# sensors.net
KiCad netlist of a schematic drawn in Altium Designer
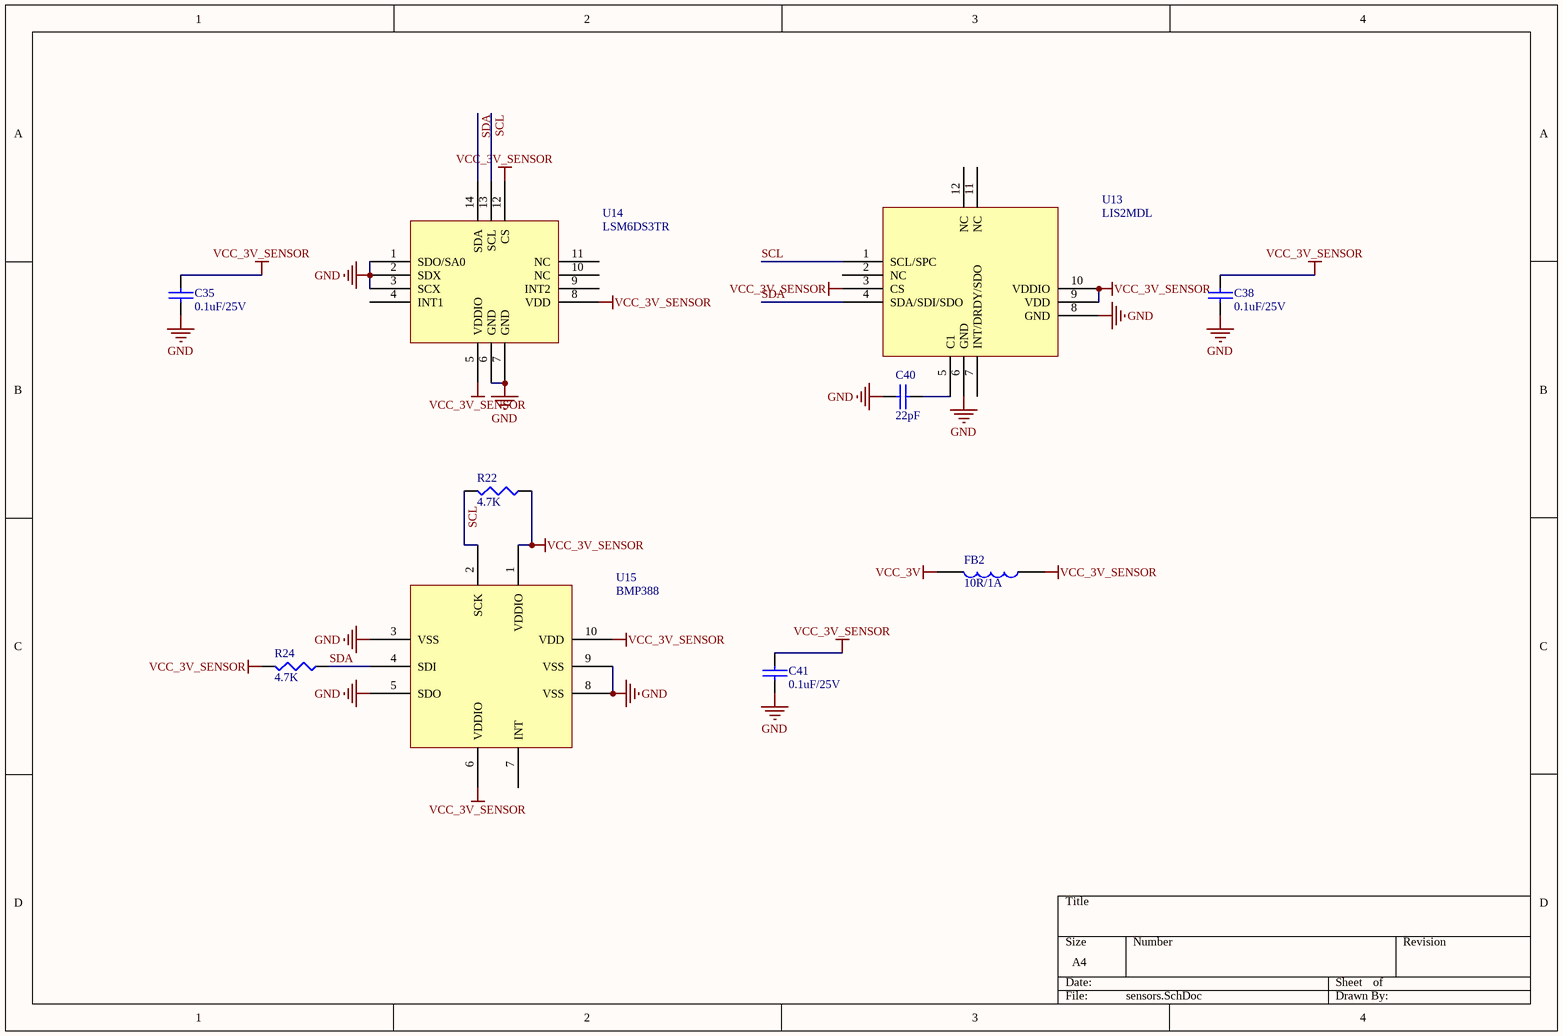
[diagram p0: sensors.SchDoc]

(export (version "E")
  (design (tool "Eeschema 10.0.6"))
  (components
    (comp (ref "C35")
      (value "0.1uF/25V")
      (footprint "0402C")
      (description "Capacitor")
      (libsource (lib "ZWLIntegrated_Library") (part "CAP"))
    )
    (comp (ref "C38")
      (value "0.1uF/25V")
      (footprint "0402C")
      (description "Capacitor")
      (libsource (lib "ZWLIntegrated_Library") (part "CAP"))
    )
    (comp (ref "C40")
      (value "22pF")
      (footprint "0402c")
      (description "Capacitor")
      (libsource (lib "SM") (part "CAP"))
    )
    (comp (ref "C41")
      (value "0.1uF/25V")
      (footprint "0402C")
      (description "Capacitor")
      (libsource (lib "ZWLIntegrated_Library") (part "CAP"))
    )
    (comp (ref "FB2") (value "10R/1A") (footprint "0603R") (libsource (lib "*") (part "INDUCTOR1")))
    (comp (ref "R22")
      (value "4.7K")
      (footprint "0402R")
      (libsource (lib "ZWLIntegrated_Library") (part "RES1"))
    )
    (comp (ref "R24")
      (value "4.7K")
      (footprint "0402R")
      (libsource (lib "ZWLIntegrated_Library") (part "RES1"))
    )
    (comp (ref "U13") (value "LIS2MDL") (footprint "LIS2MDL") (libsource (lib "stm32") (part "LIS2MDL")))
    (comp (ref "U14")
      (value "LSM6DS3TR")
      (footprint "LSM6DS3TR-C")
      (libsource (lib "stm32") (part "LSM6DS3TR"))
    )
    (comp (ref "U15") (value "BMP388") (footprint "BMP388") (libsource (lib "stm32") (part "BMP388")))
  )
  (nets
    (net (code "1") (name "/SCL") (class "Default")
      (node (ref "R22") (pin "2") (pinfunction "2_2") (pintype "passive"))
      (node (ref "U13") (pin "1") (pinfunction "SCL/SPC_1") (pintype "passive"))
      (node (ref "U14") (pin "13") (pinfunction "SCL_13") (pintype "passive"))
      (node (ref "U15") (pin "2") (pinfunction "SCK_2") (pintype "passive"))
    )
    (net (code "2") (name "/SDA") (class "Default")
      (node (ref "R24") (pin "1") (pinfunction "1_1") (pintype "passive"))
      (node (ref "U13") (pin "4") (pinfunction "SDA/SDI/SDO_4") (pintype "passive"))
      (node (ref "U14") (pin "14") (pinfunction "SDA_14") (pintype "passive"))
      (node (ref "U15") (pin "4") (pinfunction "SDI_4") (pintype "passive"))
    )
    (net (code "3") (name "GND") (class "Default")
      (node (ref "C35") (pin "1") (pinfunction "1_1") (pintype "passive"))
      (node (ref "C38") (pin "1") (pinfunction "1_1") (pintype "passive"))
      (node (ref "C40") (pin "2") (pinfunction "2_2") (pintype "passive"))
      (node (ref "C41") (pin "1") (pinfunction "1_1") (pintype "passive"))
      (node (ref "U13") (pin "6") (pinfunction "GND_6") (pintype "passive"))
      (node (ref "U13") (pin "8") (pinfunction "GND_8") (pintype "passive"))
      (node (ref "U14") (pin "1") (pinfunction "SDO/SA0_1") (pintype "passive"))
      (node (ref "U14") (pin "2") (pinfunction "SDX_2") (pintype "passive"))
      (node (ref "U14") (pin "3") (pinfunction "SCX_3") (pintype "passive"))
      (node (ref "U14") (pin "6") (pinfunction "GND_6") (pintype "passive"))
      (node (ref "U14") (pin "7") (pinfunction "GND_7") (pintype "passive"))
      (node (ref "U15") (pin "3") (pinfunction "VSS_3") (pintype "passive"))
      (node (ref "U15") (pin "5") (pinfunction "SDO_5") (pintype "passive"))
      (node (ref "U15") (pin "8") (pinfunction "VSS_8") (pintype "passive"))
      (node (ref "U15") (pin "9") (pinfunction "VSS_9") (pintype "passive"))
    )
    (net (code "4") (name "Net-(U13-C1)") (class "Default")
      (node (ref "C40") (pin "1") (pinfunction "1_1") (pintype "passive"))
      (node (ref "U13") (pin "5") (pinfunction "C1_5") (pintype "passive"))
    )
    (net (code "5") (name "VCC_3V") (class "Default")
      (node (ref "FB2") (pin "1") (pinfunction "1_1") (pintype "passive"))
    )
    (net (code "6") (name "VCC_3V_SENSOR") (class "Default")
      (node (ref "C35") (pin "2") (pinfunction "2_2") (pintype "passive"))
      (node (ref "C38") (pin "2") (pinfunction "2_2") (pintype "passive"))
      (node (ref "C41") (pin "2") (pinfunction "2_2") (pintype "passive"))
      (node (ref "FB2") (pin "2") (pinfunction "2_2") (pintype "passive"))
      (node (ref "R22") (pin "1") (pinfunction "1_1") (pintype "passive"))
      (node (ref "R24") (pin "2") (pinfunction "2_2") (pintype "passive"))
      (node (ref "U13") (pin "10") (pinfunction "VDDIO_10") (pintype "passive"))
      (node (ref "U13") (pin "3") (pinfunction "CS_3") (pintype "passive"))
      (node (ref "U13") (pin "9") (pinfunction "VDD_9") (pintype "passive"))
      (node (ref "U14") (pin "12") (pinfunction "CS_12") (pintype "passive"))
      (node (ref "U14") (pin "5") (pinfunction "VDDIO_5") (pintype "passive"))
      (node (ref "U14") (pin "8") (pinfunction "VDD_8") (pintype "passive"))
      (node (ref "U15") (pin "1") (pinfunction "VDDIO_1") (pintype "passive"))
      (node (ref "U15") (pin "10") (pinfunction "VDD_10") (pintype "passive"))
      (node (ref "U15") (pin "6") (pinfunction "VDDIO_6") (pintype "passive"))
    )
    (net (code "7") (name "unconnected-(U13-INT{slash}DRDY{slash}SDO-Pad7)") (class "Default")
      (node (ref "U13") (pin "7") (pinfunction "INT/DRDY/SDO_7") (pintype "passive"))
    )
    (net (code "8") (name "unconnected-(U13-NC-Pad2)") (class "Default")
      (node (ref "U13") (pin "2") (pinfunction "NC_2") (pintype "passive"))
    )
    (net (code "9") (name "unconnected-(U13-NC-Pad11)") (class "Default")
      (node (ref "U13") (pin "11") (pinfunction "NC_11") (pintype "passive"))
    )
    (net (code "10") (name "unconnected-(U13-NC-Pad12)") (class "Default")
      (node (ref "U13") (pin "12") (pinfunction "NC_12") (pintype "passive"))
    )
    (net (code "11") (name "unconnected-(U14-INT1-Pad4)") (class "Default")
      (node (ref "U14") (pin "4") (pinfunction "INT1_4") (pintype "passive"))
    )
    (net (code "12") (name "unconnected-(U14-INT2-Pad9)") (class "Default")
      (node (ref "U14") (pin "9") (pinfunction "INT2_9") (pintype "passive"))
    )
    (net (code "13") (name "unconnected-(U14-NC-Pad10)") (class "Default")
      (node (ref "U14") (pin "10") (pinfunction "NC_10") (pintype "passive"))
    )
    (net (code "14") (name "unconnected-(U14-NC-Pad11)") (class "Default")
      (node (ref "U14") (pin "11") (pinfunction "NC_11") (pintype "passive"))
    )
    (net (code "15") (name "unconnected-(U15-INT-Pad7)") (class "Default")
      (node (ref "U15") (pin "7") (pinfunction "INT_7") (pintype "passive"))
    )
  )
)
